# lcd.net
KiCad netlist of a schematic drawn in Altium Designer
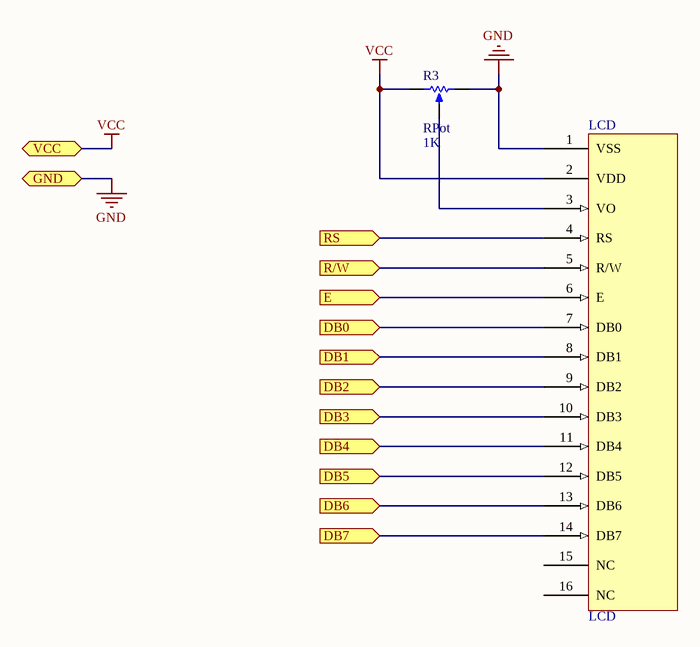
[diagram p0: lcd.SchDoc]

(export (version "E")
  (design (tool "Eeschema 10.0.6"))
  (components
    (comp (ref "LCD") (value "LCD") (footprint "IDC16") (libsource (lib "LCD") (part "LCD")))
    (comp (ref "R3")
      (value "RPot")
      (footprint "trimpot")
      (description "Potentiometer")
      (fields (field (name "ALTIUM_VALUE") "1K") (field (name "PUBLISHER") "Altium Limited"))
      (libsource (lib "Miscellaneous Devices") (part "RPot"))
    )
  )
  (nets
    (net (code "1") (name "/DB0") (class "Default")
      (node (ref "LCD") (pin "7") (pinfunction "DB0_7") (pintype "input"))
    )
    (net (code "2") (name "/DB1") (class "Default")
      (node (ref "LCD") (pin "8") (pinfunction "DB1_8") (pintype "input"))
    )
    (net (code "3") (name "/DB2") (class "Default")
      (node (ref "LCD") (pin "9") (pinfunction "DB2_9") (pintype "input"))
    )
    (net (code "4") (name "/DB3") (class "Default")
      (node (ref "LCD") (pin "10") (pinfunction "DB3_10") (pintype "input"))
    )
    (net (code "5") (name "/DB4") (class "Default")
      (node (ref "LCD") (pin "11") (pinfunction "DB4_11") (pintype "input"))
    )
    (net (code "6") (name "/DB5") (class "Default")
      (node (ref "LCD") (pin "12") (pinfunction "DB5_12") (pintype "input"))
    )
    (net (code "7") (name "/DB6") (class "Default")
      (node (ref "LCD") (pin "13") (pinfunction "DB6_13") (pintype "input"))
    )
    (net (code "8") (name "/DB7") (class "Default")
      (node (ref "LCD") (pin "14") (pinfunction "DB7_14") (pintype "input"))
    )
    (net (code "9") (name "/E") (class "Default")
      (node (ref "LCD") (pin "6") (pinfunction "E_6") (pintype "input"))
    )
    (net (code "10") (name "/RS") (class "Default")
      (node (ref "LCD") (pin "4") (pinfunction "RS_4") (pintype "input"))
    )
    (net (code "11") (name "/R{slash}W") (class "Default")
      (node (ref "LCD") (pin "5") (pinfunction "R/W_5") (pintype "input"))
    )
    (net (code "12") (name "GND") (class "Default")
      (node (ref "LCD") (pin "1") (pinfunction "VSS_1") (pintype "power_in"))
      (node (ref "R3") (pin "2") (pinfunction "BOT_2") (pintype "passive"))
    )
    (net (code "13") (name "Net-(LCD-VO)") (class "Default")
      (node (ref "LCD") (pin "3") (pinfunction "VO_3") (pintype "input"))
      (node (ref "R3") (pin "3") (pinfunction "TAP_3") (pintype "passive"))
    )
    (net (code "14") (name "VCC") (class "Default")
      (node (ref "LCD") (pin "2") (pinfunction "VDD_2") (pintype "power_in"))
      (node (ref "R3") (pin "1") (pinfunction "TOP_1") (pintype "passive"))
    )
    (net (code "15") (name "unconnected-(LCD-NC-Pad15)") (class "Default")
      (node (ref "LCD") (pin "15") (pinfunction "NC_15") (pintype "passive"))
    )
    (net (code "16") (name "unconnected-(LCD-NC-Pad16)") (class "Default")
      (node (ref "LCD") (pin "16") (pinfunction "NC_16") (pintype "passive"))
    )
  )
)
